# Band_Pass_Filter.net
KiCad netlist of a schematic drawn in Altium Designer
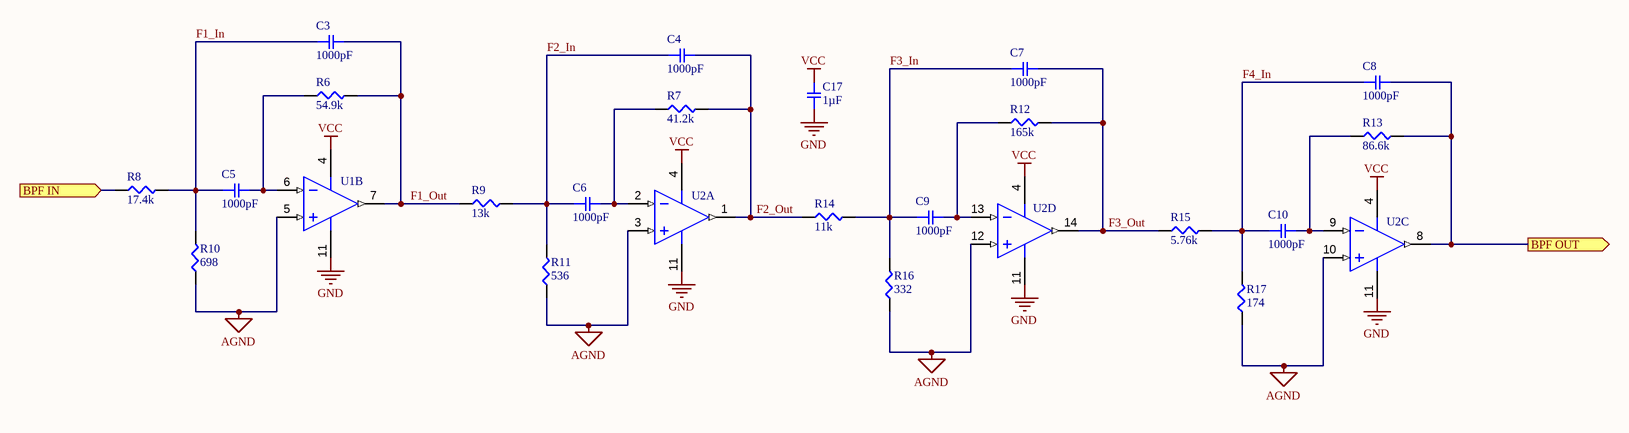
[diagram p0: Band Pass Filter.SchDoc]

(export (version "E")
  (design (tool "Eeschema 10.0.6"))
  (components
    (comp (ref "C3")
      (value "1000pF")
      (footprint "SMD-0603C")
      (description "CAP CER 1000PF 50V X7R 0603")
      (fields
        (field (name "MANUFACTURER") "Walsin Technology Corporation")
        (field (name "MANUFACTURER PART NUMBER") "0603N102F500CT")
      )
      (libsource (lib "capacitor_murata_0603") (part "GCJ188R71H102KA01D"))
    )
    (comp (ref "C4")
      (value "1000pF")
      (footprint "SMD-0603C")
      (description "CAP CER 1000PF 50V X7R 0603")
      (fields
        (field (name "MANUFACTURER") "Walsin Technology Corporation")
        (field (name "MANUFACTURER PART NUMBER") "0603N102F500CT")
      )
      (libsource (lib "capacitor_murata_0603") (part "GCJ188R71H102KA01D"))
    )
    (comp (ref "C5")
      (value "1000pF")
      (footprint "SMD-0603C")
      (description "CAP CER 1000PF 50V X7R 0603")
      (fields
        (field (name "MANUFACTURER") "Walsin Technology Corporation")
        (field (name "MANUFACTURER PART NUMBER") "0603N102F500CT")
      )
      (libsource (lib "capacitor_murata_0603") (part "GCJ188R71H102KA01D"))
    )
    (comp (ref "C6")
      (value "1000pF")
      (footprint "SMD-0603C")
      (description "CAP CER 1000PF 50V X7R 0603")
      (fields
        (field (name "MANUFACTURER") "Walsin Technology Corporation")
        (field (name "MANUFACTURER PART NUMBER") "0603N102F500CT")
      )
      (libsource (lib "capacitor_murata_0603") (part "GCJ188R71H102KA01D"))
    )
    (comp (ref "C7")
      (value "1000pF")
      (footprint "SMD-0603C")
      (description "CAP CER 1000PF 50V X7R 0603")
      (fields
        (field (name "MANUFACTURER") "Walsin Technology Corporation")
        (field (name "MANUFACTURER PART NUMBER") "0603N102F500CT")
      )
      (libsource (lib "capacitor_murata_0603") (part "GCJ188R71H102KA01D"))
    )
    (comp (ref "C8")
      (value "1000pF")
      (footprint "SMD-0603C")
      (description "CAP CER 1000PF 50V X7R 0603")
      (fields
        (field (name "MANUFACTURER") "Walsin Technology Corporation")
        (field (name "MANUFACTURER PART NUMBER") "0603N102F500CT")
      )
      (libsource (lib "capacitor_murata_0603") (part "GCJ188R71H102KA01D"))
    )
    (comp (ref "C9")
      (value "1000pF")
      (footprint "SMD-0603C")
      (description "CAP CER 1000PF 50V X7R 0603")
      (fields
        (field (name "MANUFACTURER") "Walsin Technology Corporation")
        (field (name "MANUFACTURER PART NUMBER") "0603N102F500CT")
      )
      (libsource (lib "capacitor_murata_0603") (part "GCJ188R71H102KA01D"))
    )
    (comp (ref "C10")
      (value "1000pF")
      (footprint "SMD-0603C")
      (description "CAP CER 1000PF 50V X7R 0603")
      (fields
        (field (name "MANUFACTURER") "Walsin Technology Corporation")
        (field (name "MANUFACTURER PART NUMBER") "0603N102F500CT")
      )
      (libsource (lib "capacitor_murata_0603") (part "GCJ188R71H102KA01D"))
    )
    (comp (ref "C17")
      (value "1µF")
      (footprint "SMD-0603C")
      (description "CAP CER 1UF 16V X7R 0603")
      (fields
        (field (name "MANUFACTURER") "Samsung Electro-Mechanics")
        (field (name "MANUFACTURER PART NUMBER") "CL10A105KA8NNNC")
      )
      (libsource (lib "capacitor_murata_0603") (part "GCM188R71C105KA64D"))
    )
    (comp (ref "R6")
      (value "54.9k")
      (footprint "SMD-0603-RES")
      (description "RES SMD 54.9K OHM 1% 1/10W 0603")
      (fields
        (field (name "MANUFACTURER") "Panasonic Electronic Components")
        (field (name "MANUFACTURER PART NUMBER") "ERJ-3EKF5492V")
      )
      (libsource (lib "Panasonic_resistor_0603") (part "ERJ-3EKF5492V"))
    )
    (comp (ref "R7")
      (value "41.2k")
      (footprint "SMD-0603-RES")
      (description "RES SMD 41.2K OHM 1% 1/10W 0603")
      (fields
        (field (name "MANUFACTURER") "Panasonic Electronic Components")
        (field (name "MANUFACTURER PART NUMBER") "ERJ-3EKF4122V")
      )
      (libsource (lib "Panasonic_resistor_0603") (part "ERJ-3EKF4122V"))
    )
    (comp (ref "R8")
      (value "17.4k")
      (footprint "SMD-0603-RES")
      (description "RES SMD 17.4K OHM 1% 1/10W 0603")
      (fields
        (field (name "MANUFACTURER") "Panasonic Electronic Components")
        (field (name "MANUFACTURER PART NUMBER") "ERJ-3EKF1742V")
      )
      (libsource (lib "Panasonic_resistor_0603") (part "ERJ-3EKF1742V"))
    )
    (comp (ref "R9")
      (value "13k")
      (footprint "SMD-0603-RES")
      (description "RES SMD 13K OHM 1% 1/10W 0603")
      (fields
        (field (name "MANUFACTURER") "Panasonic Electronic Components")
        (field (name "MANUFACTURER PART NUMBER") "ERJ-3EKF1302V")
      )
      (libsource (lib "Panasonic_resistor_0603") (part "ERJ-3EKF1302V"))
    )
    (comp (ref "R10")
      (value "698")
      (footprint "SMD-0603-RES")
      (description "RES SMD 698 OHM 1% 1/10W 0603")
      (fields
        (field (name "MANUFACTURER") "Panasonic Electronic Components")
        (field (name "MANUFACTURER PART NUMBER") "ERJ-3EKF6980V")
      )
      (libsource (lib "Panasonic_resistor_0603") (part "ERJ-3EKF6980V"))
    )
    (comp (ref "R11")
      (value "536")
      (footprint "SMD-0603-RES")
      (description "RES SMD 536 OHM 1% 1/10W 0603")
      (fields
        (field (name "MANUFACTURER") "Panasonic Electronic Components")
        (field (name "MANUFACTURER PART NUMBER") "ERJ-3EKF5360V")
      )
      (libsource (lib "Panasonic_resistor_0603") (part "ERJ-3EKF5360V"))
    )
    (comp (ref "R12")
      (value "165k")
      (footprint "SMD-0603-RES")
      (description "RES SMD 165K OHM 1% 1/10W 0603")
      (fields
        (field (name "MANUFACTURER") "Panasonic Electronic Components")
        (field (name "MANUFACTURER PART NUMBER") "ERJ-3EKF1653V")
      )
      (libsource (lib "Panasonic_resistor_0603") (part "ERJ-3EKF1653V"))
    )
    (comp (ref "R13")
      (value "86.6k")
      (footprint "SMD-0603-RES")
      (description "RES SMD 86.6K OHM 1% 1/10W 0603")
      (fields
        (field (name "MANUFACTURER") "Panasonic Electronic Components")
        (field (name "MANUFACTURER PART NUMBER") "ERJ-3EKF8662V")
      )
      (libsource (lib "Panasonic_resistor_0603") (part "ERJ-3EKF8662V"))
    )
    (comp (ref "R14")
      (value "11k")
      (footprint "SMD-0603-RES")
      (description "RES SMD 11K OHM 1% 1/10W 0603")
      (fields
        (field (name "MANUFACTURER") "Panasonic Electronic Components")
        (field (name "MANUFACTURER PART NUMBER") "ERJ-3EKF1102V")
      )
      (libsource (lib "Panasonic_resistor_0603") (part "ERJ-3EKF1102V"))
    )
    (comp (ref "R15")
      (value "5.76k")
      (footprint "SMD-0603-RES")
      (description "RES SMD 5.76K OHM 1% 1/10W 0603")
      (fields
        (field (name "MANUFACTURER") "Panasonic Electronic Components")
        (field (name "MANUFACTURER PART NUMBER") "ERJ-3EKF5761V")
      )
      (libsource (lib "Panasonic_resistor_0603") (part "ERJ-3EKF5761V"))
    )
    (comp (ref "R16")
      (value "332")
      (footprint "SMD-0603-RES")
      (description "RES SMD 332 OHM 1% 1/10W 0603")
      (fields
        (field (name "MANUFACTURER") "Panasonic Electronic Components")
        (field (name "MANUFACTURER PART NUMBER") "ERJ-3EKF3320V")
      )
      (libsource (lib "Panasonic_resistor_0603") (part "ERJ-3EKF3320V"))
    )
    (comp (ref "R17")
      (value "174")
      (footprint "SMD-0603-RES")
      (description "RES SMD 174 OHM 1% 1/10W 0603")
      (fields
        (field (name "MANUFACTURER") "Panasonic Electronic Components")
        (field (name "MANUFACTURER PART NUMBER") "ERJ-3EKF1740V")
      )
      (libsource (lib "Panasonic_resistor_0603") (part "ERJ-3EKF1740V"))
    )
    (comp (ref "U1")
      (value "OPA1604AIPWR")
      (footprint "PW0014A_N")
      (fields (field (name "MANUFACTURER") "Texas Instruments"))
      (libsource (lib "Altium Content Vault") (part "TI-OPA16X4_4XXX-14"))
    )
    (comp (ref "U2")
      (value "OPA1604AIPWR")
      (footprint "PW0014A_N")
      (fields (field (name "MANUFACTURER") "Texas Instruments"))
      (libsource (lib "Altium Content Vault") (part "TI-OPA16X4_4XXX-14"))
    )
  )
  (nets
    (net (code "1") (name "/BPF IN") (class "Default")
      (node (ref "R8") (pin "1") (pinfunction "1_1") (pintype "passive"))
    )
    (net (code "2") (name "/BPF OUT") (class "Default")
      (node (ref "C8") (pin "2") (pinfunction "2_2") (pintype "passive"))
      (node (ref "R13") (pin "2") (pinfunction "2_2") (pintype "passive"))
      (node (ref "U2") (pin "8") (pinfunction "OUT_C_8") (pintype "output"))
    )
    (net (code "3") (name "/F1_In") (class "Default")
      (node (ref "C3") (pin "1") (pinfunction "1_1") (pintype "passive"))
      (node (ref "C5") (pin "1") (pinfunction "1_1") (pintype "passive"))
      (node (ref "R10") (pin "2") (pinfunction "2_2") (pintype "passive"))
      (node (ref "R8") (pin "2") (pinfunction "2_2") (pintype "passive"))
    )
    (net (code "4") (name "/F1_Out") (class "Default")
      (node (ref "C3") (pin "2") (pinfunction "2_2") (pintype "passive"))
      (node (ref "R6") (pin "2") (pinfunction "2_2") (pintype "passive"))
      (node (ref "R9") (pin "1") (pinfunction "1_1") (pintype "passive"))
      (node (ref "U1") (pin "7") (pinfunction "OUT_B_7") (pintype "output"))
    )
    (net (code "5") (name "/F2_In") (class "Default")
      (node (ref "C4") (pin "1") (pinfunction "1_1") (pintype "passive"))
      (node (ref "C6") (pin "1") (pinfunction "1_1") (pintype "passive"))
      (node (ref "R11") (pin "2") (pinfunction "2_2") (pintype "passive"))
      (node (ref "R9") (pin "2") (pinfunction "2_2") (pintype "passive"))
    )
    (net (code "6") (name "/F2_Out") (class "Default")
      (node (ref "C4") (pin "2") (pinfunction "2_2") (pintype "passive"))
      (node (ref "R14") (pin "1") (pinfunction "1_1") (pintype "passive"))
      (node (ref "R7") (pin "2") (pinfunction "2_2") (pintype "passive"))
      (node (ref "U2") (pin "1") (pinfunction "OUT_A_1") (pintype "output"))
    )
    (net (code "7") (name "/F3_In") (class "Default")
      (node (ref "C7") (pin "1") (pinfunction "1_1") (pintype "passive"))
      (node (ref "C9") (pin "1") (pinfunction "1_1") (pintype "passive"))
      (node (ref "R14") (pin "2") (pinfunction "2_2") (pintype "passive"))
      (node (ref "R16") (pin "2") (pinfunction "2_2") (pintype "passive"))
    )
    (net (code "8") (name "/F3_Out") (class "Default")
      (node (ref "C7") (pin "2") (pinfunction "2_2") (pintype "passive"))
      (node (ref "R12") (pin "2") (pinfunction "2_2") (pintype "passive"))
      (node (ref "R15") (pin "1") (pinfunction "1_1") (pintype "passive"))
      (node (ref "U2") (pin "14") (pinfunction "OUT_D_14") (pintype "output"))
    )
    (net (code "9") (name "/F4_In") (class "Default")
      (node (ref "C10") (pin "1") (pinfunction "1_1") (pintype "passive"))
      (node (ref "C8") (pin "1") (pinfunction "1_1") (pintype "passive"))
      (node (ref "R15") (pin "2") (pinfunction "2_2") (pintype "passive"))
      (node (ref "R17") (pin "2") (pinfunction "2_2") (pintype "passive"))
    )
    (net (code "10") (name "AGND") (class "Default")
      (node (ref "R10") (pin "1") (pinfunction "1_1") (pintype "passive"))
      (node (ref "R11") (pin "1") (pinfunction "1_1") (pintype "passive"))
      (node (ref "R16") (pin "1") (pinfunction "1_1") (pintype "passive"))
      (node (ref "R17") (pin "1") (pinfunction "1_1") (pintype "passive"))
      (node (ref "U1") (pin "5") (pinfunction "IN_B+_5") (pintype "input"))
      (node (ref "U2") (pin "10") (pinfunction "IN_C+_10") (pintype "input"))
      (node (ref "U2") (pin "12") (pinfunction "IN_D+_12") (pintype "input"))
      (node (ref "U2") (pin "3") (pinfunction "IN_A+_3") (pintype "input"))
    )
    (net (code "11") (name "GND") (class "Default")
      (node (ref "C17") (pin "1") (pinfunction "1_1") (pintype "passive"))
      (node (ref "U1") (pin "11") (pinfunction "V-_11") (pintype "power_in"))
      (node (ref "U2") (pin "11") (pinfunction "V-_11") (pintype "power_in"))
    )
    (net (code "12") (name "Net-(U1B-IN_B-)") (class "Default")
      (node (ref "C5") (pin "2") (pinfunction "2_2") (pintype "passive"))
      (node (ref "R6") (pin "1") (pinfunction "1_1") (pintype "passive"))
      (node (ref "U1") (pin "6") (pinfunction "IN_B-_6") (pintype "input"))
    )
    (net (code "13") (name "Net-(U2A-IN_A-)") (class "Default")
      (node (ref "C6") (pin "2") (pinfunction "2_2") (pintype "passive"))
      (node (ref "R7") (pin "1") (pinfunction "1_1") (pintype "passive"))
      (node (ref "U2") (pin "2") (pinfunction "IN_A-_2") (pintype "input"))
    )
    (net (code "14") (name "Net-(U2C-IN_C-)") (class "Default")
      (node (ref "C10") (pin "2") (pinfunction "2_2") (pintype "passive"))
      (node (ref "R13") (pin "1") (pinfunction "1_1") (pintype "passive"))
      (node (ref "U2") (pin "9") (pinfunction "IN_C-_9") (pintype "input"))
    )
    (net (code "15") (name "Net-(U2D-IN_D-)") (class "Default")
      (node (ref "C9") (pin "2") (pinfunction "2_2") (pintype "passive"))
      (node (ref "R12") (pin "1") (pinfunction "1_1") (pintype "passive"))
      (node (ref "U2") (pin "13") (pinfunction "IN_D-_13") (pintype "input"))
    )
    (net (code "16") (name "VCC") (class "Default")
      (node (ref "C17") (pin "2") (pinfunction "2_2") (pintype "passive"))
      (node (ref "U1") (pin "4") (pinfunction "V+_4") (pintype "power_in"))
      (node (ref "U2") (pin "4") (pinfunction "V+_4") (pintype "power_in"))
    )
  )
)
